# raspberrypi_to_ws2801_v4.net
KiCad netlist of a schematic drawn in EAGLE
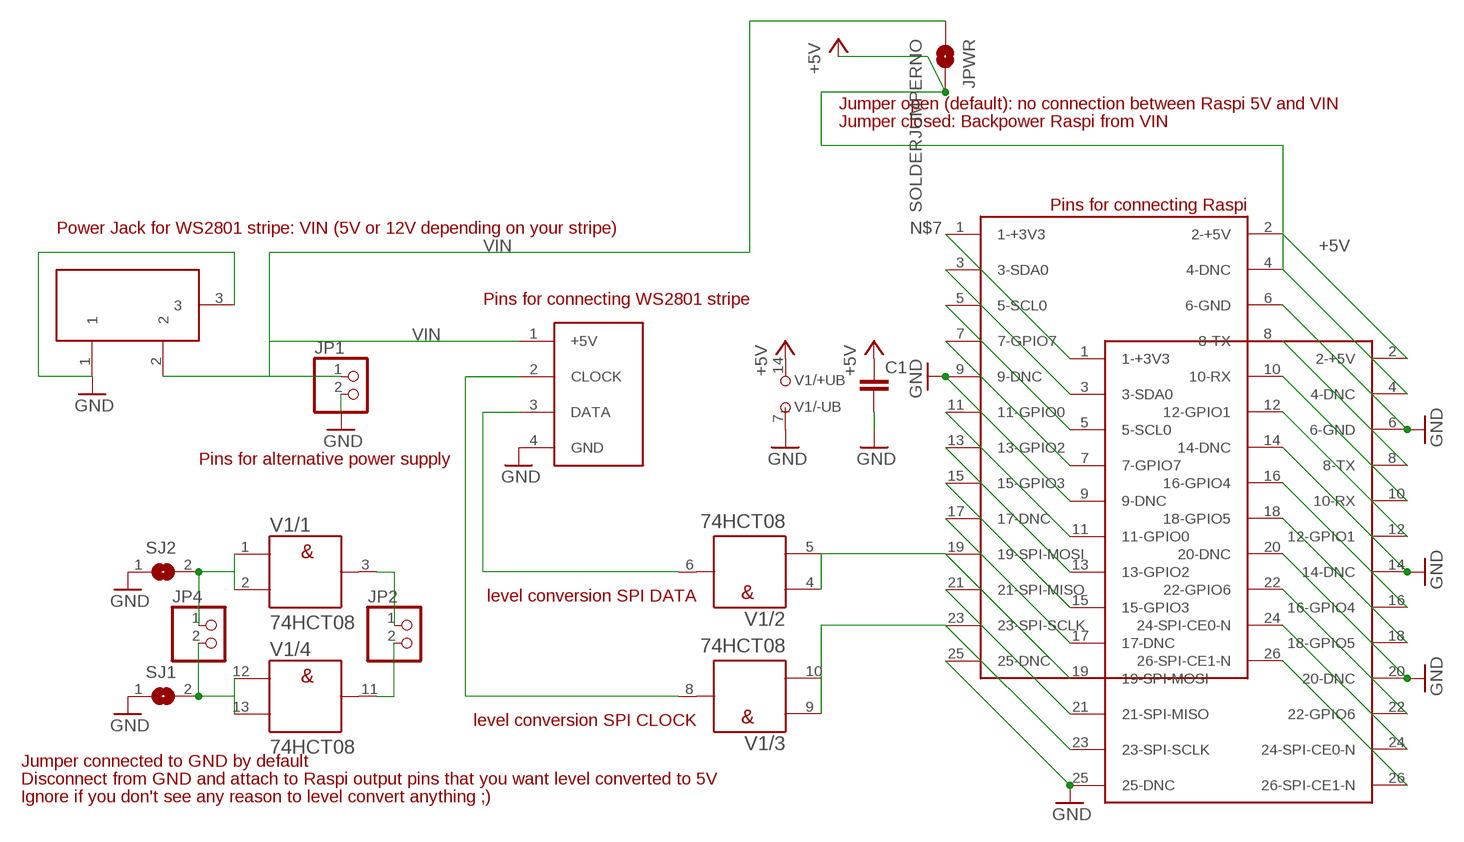
[diagram p0: schematic, sheet 1]

(export (version "E")
  (design (tool "Eeschema 10.0.6"))
  (components
    (comp (ref "C1")
      (value "C-EU025-024X044")
      (footprint "eagle-import:C025-024X044")
      (libsource (lib "eagle-import") (part "C-EU025-024X044"))
    )
    (comp (ref "JP1")
      (value "PINHD-1X2")
      (footprint "eagle-import:1X02")
      (libsource (lib "eagle-import") (part "PINHD-1X2"))
    )
    (comp (ref "JP2")
      (value "PINHD-1X2")
      (footprint "eagle-import:1X02")
      (libsource (lib "eagle-import") (part "pins_PINHD-1X2"))
    )
    (comp (ref "JP4")
      (value "PINHD-1X2")
      (footprint "eagle-import:1X02")
      (libsource (lib "eagle-import") (part "pins_PINHD-1X2"))
    )
    (comp (ref "JPWR")
      (value "SOLDERJUMPERNO")
      (footprint "eagle-import:SJ_2S-NO")
      (libsource (lib "eagle-import") (part "SOLDERJUMPERNO"))
    )
    (comp (ref "SJ1") (value "SJ") (footprint "eagle-import:SJ") (libsource (lib "eagle-import") (part "SJ")))
    (comp (ref "SJ2") (value "SJ") (footprint "eagle-import:SJ") (libsource (lib "eagle-import") (part "SJ")))
    (comp (ref "U$1")
      (value "RASPBERRY-PI")
      (footprint "eagle-import:RASPBERRY-PI")
      (libsource (lib "eagle-import") (part "RASPBERRY-PI"))
    )
    (comp (ref "U$2")
      (value "RASPBERRY-PI")
      (footprint "eagle-import:RASPBERRY-PI")
      (libsource (lib "eagle-import") (part "RASPBERRY-PI"))
    )
    (comp (ref "U$3")
      (value "W2801STRIP")
      (footprint "eagle-import:1X04")
      (libsource (lib "eagle-import") (part "W2801STRIP"))
    )
    (comp (ref "U$5")
      (value "DC21MMX")
      (footprint "eagle-import:DC-21MM")
      (libsource (lib "eagle-import") (part "DC21MMX"))
    )
    (comp (ref "V1")
      (value "74HCT08")
      (footprint "eagle-import:DIL14")
      (libsource (lib "eagle-import") (part "7408N"))
    )
  )
  (nets
    (net (code "1") (name "+5V") (class "Default")
      (node (ref "C1") (pin "1") (pinfunction "1_1") (pintype "passive"))
      (node (ref "JPWR") (pin "2") (pinfunction "2_2") (pintype "passive"))
      (node (ref "U$1") (pin "2") (pinfunction "2-+5V_2") (pintype "bidirectional"))
      (node (ref "U$1") (pin "4") (pinfunction "4-DNC_4") (pintype "bidirectional"))
      (node (ref "U$2") (pin "2") (pinfunction "2-+5V_2") (pintype "bidirectional"))
      (node (ref "U$2") (pin "4") (pinfunction "4-DNC_4") (pintype "bidirectional"))
      (node (ref "V1") (pin "14") (pinfunction "+UB_14") (pintype "power_in"))
    )
    (net (code "2") (name "/N$7") (class "Default")
      (node (ref "U$1") (pin "1") (pinfunction "1-+3V3_1") (pintype "bidirectional"))
      (node (ref "U$2") (pin "1") (pinfunction "1-+3V3_1") (pintype "bidirectional"))
    )
    (net (code "3") (name "/VIN") (class "Default")
      (node (ref "JP1") (pin "1") (pinfunction "1_1") (pintype "passive"))
      (node (ref "JPWR") (pin "1") (pinfunction "1_1") (pintype "passive"))
      (node (ref "U$3") (pin "1") (pinfunction "+5V_1") (pintype "bidirectional"))
      (node (ref "U$5") (pin "2") (pinfunction "2_2") (pintype "power_in"))
    )
    (net (code "4") (name "GND") (class "Default")
      (node (ref "C1") (pin "2") (pinfunction "2_2") (pintype "passive"))
      (node (ref "JP1") (pin "2") (pinfunction "2_2") (pintype "passive"))
      (node (ref "SJ1") (pin "1") (pinfunction "1_1") (pintype "passive"))
      (node (ref "SJ2") (pin "1") (pinfunction "1_1") (pintype "passive"))
      (node (ref "U$1") (pin "14") (pinfunction "14-DNC_14") (pintype "bidirectional"))
      (node (ref "U$1") (pin "20") (pinfunction "20-DNC_20") (pintype "bidirectional"))
      (node (ref "U$1") (pin "25") (pinfunction "25-DNC_25") (pintype "bidirectional"))
      (node (ref "U$1") (pin "6") (pinfunction "6-GND_6") (pintype "bidirectional"))
      (node (ref "U$1") (pin "9") (pinfunction "9-DNC_9") (pintype "bidirectional"))
      (node (ref "U$2") (pin "14") (pinfunction "14-DNC_14") (pintype "bidirectional"))
      (node (ref "U$2") (pin "20") (pinfunction "20-DNC_20") (pintype "bidirectional"))
      (node (ref "U$2") (pin "25") (pinfunction "25-DNC_25") (pintype "bidirectional"))
      (node (ref "U$2") (pin "6") (pinfunction "6-GND_6") (pintype "bidirectional"))
      (node (ref "U$2") (pin "9") (pinfunction "9-DNC_9") (pintype "bidirectional"))
      (node (ref "U$3") (pin "4") (pinfunction "GND_4") (pintype "bidirectional"))
      (node (ref "U$5") (pin "1") (pinfunction "1_1") (pintype "power_in"))
      (node (ref "U$5") (pin "3") (pinfunction "3_3") (pintype "power_in"))
      (node (ref "V1") (pin "7") (pinfunction "-UB_7") (pintype "power_in"))
    )
    (net (code "5") (name "Net-(U$1-3-SDA0)") (class "Default")
      (node (ref "U$1") (pin "3") (pinfunction "3-SDA0_3") (pintype "bidirectional"))
      (node (ref "U$2") (pin "3") (pinfunction "3-SDA0_3") (pintype "bidirectional"))
    )
    (net (code "6") (name "Net-(U$1-5-SCL0)") (class "Default")
      (node (ref "U$1") (pin "5") (pinfunction "5-SCL0_5") (pintype "bidirectional"))
      (node (ref "U$2") (pin "5") (pinfunction "5-SCL0_5") (pintype "bidirectional"))
    )
    (net (code "7") (name "Net-(U$1-7-GPIO7)") (class "Default")
      (node (ref "U$1") (pin "7") (pinfunction "7-GPIO7_7") (pintype "bidirectional"))
      (node (ref "U$2") (pin "7") (pinfunction "7-GPIO7_7") (pintype "bidirectional"))
    )
    (net (code "8") (name "Net-(U$1-8-TX)") (class "Default")
      (node (ref "U$1") (pin "8") (pinfunction "8-TX_8") (pintype "bidirectional"))
      (node (ref "U$2") (pin "8") (pinfunction "8-TX_8") (pintype "bidirectional"))
    )
    (net (code "9") (name "Net-(U$1-10-RX)") (class "Default")
      (node (ref "U$1") (pin "10") (pinfunction "10-RX_10") (pintype "bidirectional"))
      (node (ref "U$2") (pin "10") (pinfunction "10-RX_10") (pintype "bidirectional"))
    )
    (net (code "10") (name "Net-(U$1-11-GPIO0)") (class "Default")
      (node (ref "U$1") (pin "11") (pinfunction "11-GPIO0_11") (pintype "bidirectional"))
      (node (ref "U$2") (pin "11") (pinfunction "11-GPIO0_11") (pintype "bidirectional"))
    )
    (net (code "11") (name "Net-(U$1-12-GPIO1)") (class "Default")
      (node (ref "U$1") (pin "12") (pinfunction "12-GPIO1_12") (pintype "bidirectional"))
      (node (ref "U$2") (pin "12") (pinfunction "12-GPIO1_12") (pintype "bidirectional"))
    )
    (net (code "12") (name "Net-(U$1-13-GPIO2)") (class "Default")
      (node (ref "U$1") (pin "13") (pinfunction "13-GPIO2_13") (pintype "bidirectional"))
      (node (ref "U$2") (pin "13") (pinfunction "13-GPIO2_13") (pintype "bidirectional"))
    )
    (net (code "13") (name "Net-(U$1-15-GPIO3)") (class "Default")
      (node (ref "U$1") (pin "15") (pinfunction "15-GPIO3_15") (pintype "bidirectional"))
      (node (ref "U$2") (pin "15") (pinfunction "15-GPIO3_15") (pintype "bidirectional"))
    )
    (net (code "14") (name "Net-(U$1-16-GPIO4)") (class "Default")
      (node (ref "U$1") (pin "16") (pinfunction "16-GPIO4_16") (pintype "bidirectional"))
      (node (ref "U$2") (pin "16") (pinfunction "16-GPIO4_16") (pintype "bidirectional"))
    )
    (net (code "15") (name "Net-(U$1-17-DNC)") (class "Default")
      (node (ref "U$1") (pin "17") (pinfunction "17-DNC_17") (pintype "bidirectional"))
      (node (ref "U$2") (pin "17") (pinfunction "17-DNC_17") (pintype "bidirectional"))
    )
    (net (code "16") (name "Net-(U$1-18-GPIO5)") (class "Default")
      (node (ref "U$1") (pin "18") (pinfunction "18-GPIO5_18") (pintype "bidirectional"))
      (node (ref "U$2") (pin "18") (pinfunction "18-GPIO5_18") (pintype "bidirectional"))
    )
    (net (code "17") (name "Net-(U$1-19-SPI-MOSI)") (class "Default")
      (node (ref "U$1") (pin "19") (pinfunction "19-SPI-MOSI_19") (pintype "bidirectional"))
      (node (ref "U$2") (pin "19") (pinfunction "19-SPI-MOSI_19") (pintype "bidirectional"))
      (node (ref "V1") (pin "4") (pinfunction "A_4") (pintype "input"))
      (node (ref "V1") (pin "5") (pinfunction "B_5") (pintype "input"))
    )
    (net (code "18") (name "Net-(U$1-21-SPI-MISO)") (class "Default")
      (node (ref "U$1") (pin "21") (pinfunction "21-SPI-MISO_21") (pintype "bidirectional"))
      (node (ref "U$2") (pin "21") (pinfunction "21-SPI-MISO_21") (pintype "bidirectional"))
    )
    (net (code "19") (name "Net-(U$1-22-GPIO6)") (class "Default")
      (node (ref "U$1") (pin "22") (pinfunction "22-GPIO6_22") (pintype "bidirectional"))
      (node (ref "U$2") (pin "22") (pinfunction "22-GPIO6_22") (pintype "bidirectional"))
    )
    (net (code "20") (name "Net-(U$1-23-SPI-SCLK)") (class "Default")
      (node (ref "U$1") (pin "23") (pinfunction "23-SPI-SCLK_23") (pintype "bidirectional"))
      (node (ref "U$2") (pin "23") (pinfunction "23-SPI-SCLK_23") (pintype "bidirectional"))
      (node (ref "V1") (pin "10") (pinfunction "B_10") (pintype "input"))
      (node (ref "V1") (pin "9") (pinfunction "A_9") (pintype "input"))
    )
    (net (code "21") (name "Net-(U$1-24-SPI-CE0-N)") (class "Default")
      (node (ref "U$1") (pin "24") (pinfunction "24-SPI-CE0-N_24") (pintype "bidirectional"))
      (node (ref "U$2") (pin "24") (pinfunction "24-SPI-CE0-N_24") (pintype "bidirectional"))
    )
    (net (code "22") (name "Net-(U$1-26-SPI-CE1-N)") (class "Default")
      (node (ref "U$1") (pin "26") (pinfunction "26-SPI-CE1-N_26") (pintype "bidirectional"))
      (node (ref "U$2") (pin "26") (pinfunction "26-SPI-CE1-N_26") (pintype "bidirectional"))
    )
    (net (code "23") (name "Net-(U$3-CLOCK)") (class "Default")
      (node (ref "U$3") (pin "2") (pinfunction "CLOCK_2") (pintype "bidirectional"))
      (node (ref "V1") (pin "8") (pinfunction "Y_8") (pintype "output"))
    )
    (net (code "24") (name "Net-(U$3-DATA)") (class "Default")
      (node (ref "U$3") (pin "3") (pinfunction "DATA_3") (pintype "bidirectional"))
      (node (ref "V1") (pin "6") (pinfunction "Y_6") (pintype "output"))
    )
    (net (code "25") (name "Net-(V1C-A)") (class "Default")
      (node (ref "JP4") (pin "1") (pinfunction "1_1") (pintype "passive"))
      (node (ref "SJ2") (pin "2") (pinfunction "2_2") (pintype "passive"))
      (node (ref "V1") (pin "1") (pinfunction "A_1") (pintype "input"))
      (node (ref "V1") (pin "2") (pinfunction "B_2") (pintype "input"))
    )
    (net (code "26") (name "Net-(V1C-Y)") (class "Default")
      (node (ref "JP2") (pin "1") (pinfunction "1_1") (pintype "passive"))
      (node (ref "V1") (pin "3") (pinfunction "Y_3") (pintype "output"))
    )
    (net (code "27") (name "Net-(V1F-A)") (class "Default")
      (node (ref "JP4") (pin "2") (pinfunction "2_2") (pintype "passive"))
      (node (ref "SJ1") (pin "2") (pinfunction "2_2") (pintype "passive"))
      (node (ref "V1") (pin "12") (pinfunction "A_12") (pintype "input"))
      (node (ref "V1") (pin "13") (pinfunction "B_13") (pintype "input"))
    )
    (net (code "28") (name "Net-(V1F-Y)") (class "Default")
      (node (ref "JP2") (pin "2") (pinfunction "2_2") (pintype "passive"))
      (node (ref "V1") (pin "11") (pinfunction "Y_11") (pintype "output"))
    )
  )
)
